# largemoteino1_1.net
KiCad netlist of a schematic drawn in EAGLE
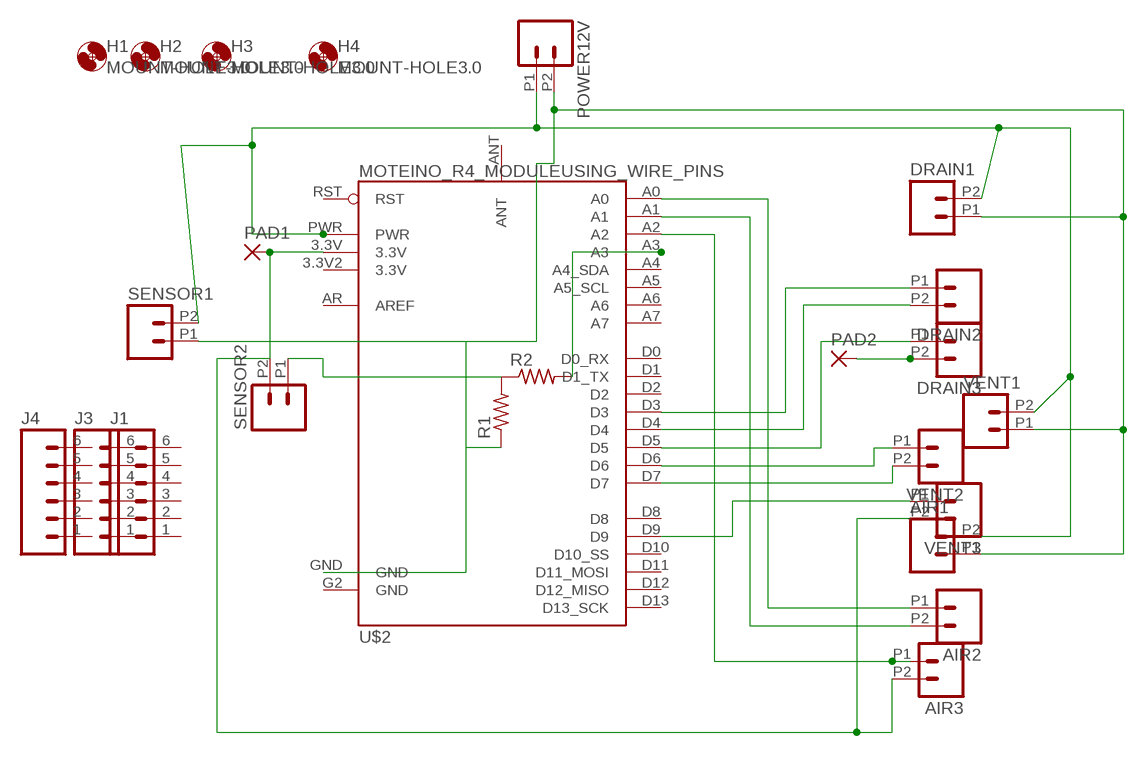
[diagram p0: schematic, sheet 1]

(export (version "E")
  (design (tool "Eeschema 10.0.6"))
  (components
    (comp (ref "AIR1")
      (value "M022.54MM_SCREWTERM")
      (footprint "eagle-import:1X02_2.54_SCREWTERM")
      (libsource (lib "eagle-import") (part "M022.54MM_SCREWTERM"))
    )
    (comp (ref "AIR2")
      (value "M022.54MM_SCREWTERM")
      (footprint "eagle-import:1X02_2.54_SCREWTERM")
      (libsource (lib "eagle-import") (part "M022.54MM_SCREWTERM"))
    )
    (comp (ref "AIR3")
      (value "M022.54MM_SCREWTERM")
      (footprint "eagle-import:1X02_2.54_SCREWTERM")
      (libsource (lib "eagle-import") (part "M022.54MM_SCREWTERM"))
    )
    (comp (ref "DRAIN1")
      (value "M022.54MM_SCREWTERM")
      (footprint "eagle-import:1X02_2.54_SCREWTERM")
      (libsource (lib "eagle-import") (part "M022.54MM_SCREWTERM"))
    )
    (comp (ref "DRAIN2")
      (value "M022.54MM_SCREWTERM")
      (footprint "eagle-import:1X02_2.54_SCREWTERM")
      (libsource (lib "eagle-import") (part "M022.54MM_SCREWTERM"))
    )
    (comp (ref "DRAIN3")
      (value "M022.54MM_SCREWTERM")
      (footprint "eagle-import:1X02_2.54_SCREWTERM")
      (libsource (lib "eagle-import") (part "M022.54MM_SCREWTERM"))
    )
    (comp (ref "H1")
      (value "MOUNT-HOLE3.0")
      (footprint "eagle-import:3,0")
      (libsource (lib "eagle-import") (part "MOUNT-HOLE3.0"))
    )
    (comp (ref "H2")
      (value "MOUNT-HOLE3.0")
      (footprint "eagle-import:3,0")
      (libsource (lib "eagle-import") (part "MOUNT-HOLE3.0"))
    )
    (comp (ref "H3")
      (value "MOUNT-HOLE3.0")
      (footprint "eagle-import:3,0")
      (libsource (lib "eagle-import") (part "MOUNT-HOLE3.0"))
    )
    (comp (ref "H4")
      (value "MOUNT-HOLE3.0")
      (footprint "eagle-import:3,0")
      (libsource (lib "eagle-import") (part "MOUNT-HOLE3.0"))
    )
    (comp (ref "J1")
      (value "M06LOCK_LONGPADS")
      (footprint "eagle-import:1X06_LOCK_LONGPADS")
      (libsource (lib "eagle-import") (part "M06LOCK_LONGPADS"))
    )
    (comp (ref "J3")
      (value "M06LOCK_LONGPADS")
      (footprint "eagle-import:1X06_LOCK_LONGPADS")
      (libsource (lib "eagle-import") (part "M06LOCK_LONGPADS"))
    )
    (comp (ref "J4")
      (value "M06LOCK_LONGPADS")
      (footprint "eagle-import:1X06_LOCK_LONGPADS")
      (libsource (lib "eagle-import") (part "M06LOCK_LONGPADS"))
    )
    (comp (ref "PAD1")
      (value "2,15/1,0")
      (footprint "eagle-import:2,15_1,0")
      (libsource (lib "eagle-import") (part "2,15/1,0"))
    )
    (comp (ref "PAD2")
      (value "2,15/1,0")
      (footprint "eagle-import:2,15_1,0")
      (libsource (lib "eagle-import") (part "2,15/1,0"))
    )
    (comp (ref "POWER12V")
      (value "M022.54MM_SCREWTERM")
      (footprint "eagle-import:1X02_2.54_SCREWTERM")
      (libsource (lib "eagle-import") (part "M022.54MM_SCREWTERM"))
    )
    (comp (ref "R1")
      (value "R-US_0207/10")
      (footprint "eagle-import:0207_10")
      (libsource (lib "eagle-import") (part "R-US_0207/10"))
    )
    (comp (ref "R2")
      (value "R-US_0207/10")
      (footprint "eagle-import:0207_10")
      (libsource (lib "eagle-import") (part "R-US_0207/10"))
    )
    (comp (ref "SENSOR1")
      (value "M022.54MM_SCREWTERM")
      (footprint "eagle-import:1X02_2.54_SCREWTERM")
      (libsource (lib "eagle-import") (part "M022.54MM_SCREWTERM"))
    )
    (comp (ref "SENSOR2")
      (value "M022.54MM_SCREWTERM")
      (footprint "eagle-import:1X02_2.54_SCREWTERM")
      (libsource (lib "eagle-import") (part "M022.54MM_SCREWTERM"))
    )
    (comp (ref "U$2")
      (value "MOTEINO_R4_MODULEUSING_WIRE_PINS")
      (footprint "eagle-import:MOTEINO_R4_WIRE")
      (libsource (lib "eagle-import") (part "MOTEINO_R4_MODULEUSING_WIRE_PINS"))
    )
    (comp (ref "VENT1")
      (value "M022.54MM_SCREWTERM")
      (footprint "eagle-import:1X02_2.54_SCREWTERM")
      (libsource (lib "eagle-import") (part "M022.54MM_SCREWTERM"))
    )
    (comp (ref "VENT2")
      (value "M022.54MM_SCREWTERM")
      (footprint "eagle-import:1X02_2.54_SCREWTERM")
      (libsource (lib "eagle-import") (part "M022.54MM_SCREWTERM"))
    )
    (comp (ref "VENT3")
      (value "M022.54MM_SCREWTERM")
      (footprint "eagle-import:1X02_2.54_SCREWTERM")
      (libsource (lib "eagle-import") (part "M022.54MM_SCREWTERM"))
    )
  )
  (nets
    (net (code "1") (name "/GND") (class "Default")
      (node (ref "U$2") (pin "G2") (pinfunction "GND_G2") (pintype "power_in"))
    )
    (net (code "2") (name "Net-(AIR1-1)") (class "Default")
      (node (ref "AIR1") (pin "P1") (pinfunction "1_P1") (pintype "passive"))
      (node (ref "DRAIN1") (pin "P1") (pinfunction "1_P1") (pintype "passive"))
      (node (ref "POWER12V") (pin "P2") (pinfunction "2_P2") (pintype "passive"))
      (node (ref "R1") (pin "1") (pinfunction "1_1") (pintype "passive"))
      (node (ref "SENSOR1") (pin "P1") (pinfunction "1_P1") (pintype "passive"))
      (node (ref "U$2") (pin "GND") (pinfunction "GND_GND") (pintype "power_in"))
      (node (ref "VENT1") (pin "P1") (pinfunction "1_P1") (pintype "passive"))
    )
    (net (code "3") (name "Net-(AIR1-2)") (class "Default")
      (node (ref "AIR1") (pin "P2") (pinfunction "2_P2") (pintype "passive"))
      (node (ref "DRAIN1") (pin "P2") (pinfunction "2_P2") (pintype "passive"))
      (node (ref "POWER12V") (pin "P1") (pinfunction "1_P1") (pintype "passive"))
      (node (ref "SENSOR1") (pin "P2") (pinfunction "2_P2") (pintype "passive"))
      (node (ref "U$2") (pin "PWR") (pinfunction "PWR_PWR") (pintype "passive"))
      (node (ref "VENT1") (pin "P2") (pinfunction "2_P2") (pintype "passive"))
    )
    (net (code "4") (name "Net-(AIR2-1)") (class "Default")
      (node (ref "AIR2") (pin "P1") (pinfunction "1_P1") (pintype "passive"))
      (node (ref "U$2") (pin "A0") (pinfunction "A0_A0") (pintype "bidirectional"))
    )
    (net (code "5") (name "Net-(AIR2-2)") (class "Default")
      (node (ref "AIR2") (pin "P2") (pinfunction "2_P2") (pintype "passive"))
      (node (ref "U$2") (pin "A1") (pinfunction "A1_A1") (pintype "bidirectional"))
    )
    (net (code "6") (name "Net-(AIR3-1)") (class "Default")
      (node (ref "AIR3") (pin "P1") (pinfunction "1_P1") (pintype "passive"))
      (node (ref "U$2") (pin "A2") (pinfunction "A2_A2") (pintype "bidirectional"))
    )
    (net (code "7") (name "Net-(AIR3-2)") (class "Default")
      (node (ref "AIR3") (pin "P2") (pinfunction "2_P2") (pintype "passive"))
      (node (ref "PAD1") (pin "1") (pinfunction "P_1") (pintype "passive"))
      (node (ref "SENSOR2") (pin "P2") (pinfunction "2_P2") (pintype "passive"))
      (node (ref "U$2") (pin "3.3V") (pinfunction "3.3V_3.3V") (pintype "passive"))
      (node (ref "VENT3") (pin "P2") (pinfunction "2_P2") (pintype "passive"))
    )
    (net (code "8") (name "Net-(DRAIN2-1)") (class "Default")
      (node (ref "DRAIN2") (pin "P1") (pinfunction "1_P1") (pintype "passive"))
      (node (ref "U$2") (pin "D3") (pinfunction "D3_D3") (pintype "bidirectional"))
    )
    (net (code "9") (name "Net-(DRAIN2-2)") (class "Default")
      (node (ref "DRAIN2") (pin "P2") (pinfunction "2_P2") (pintype "passive"))
      (node (ref "U$2") (pin "D4") (pinfunction "D4_D4") (pintype "bidirectional"))
    )
    (net (code "10") (name "Net-(DRAIN3-1)") (class "Default")
      (node (ref "DRAIN3") (pin "P1") (pinfunction "1_P1") (pintype "passive"))
      (node (ref "U$2") (pin "D5") (pinfunction "D5_D5") (pintype "bidirectional"))
    )
    (net (code "11") (name "Net-(DRAIN3-2)") (class "Default")
      (node (ref "DRAIN3") (pin "P2") (pinfunction "2_P2") (pintype "passive"))
      (node (ref "PAD2") (pin "1") (pinfunction "P_1") (pintype "passive"))
    )
    (net (code "12") (name "Net-(R2-Pad2)") (class "Default")
      (node (ref "R2") (pin "2") (pinfunction "2_2") (pintype "passive"))
      (node (ref "U$2") (pin "A3") (pinfunction "A3_A3") (pintype "bidirectional"))
    )
    (net (code "13") (name "Net-(SENSOR2-1)") (class "Default")
      (node (ref "R1") (pin "2") (pinfunction "2_2") (pintype "passive"))
      (node (ref "R2") (pin "1") (pinfunction "1_1") (pintype "passive"))
      (node (ref "SENSOR2") (pin "P1") (pinfunction "1_P1") (pintype "passive"))
    )
    (net (code "14") (name "Net-(VENT2-1)") (class "Default")
      (node (ref "U$2") (pin "D6") (pinfunction "D6_D6") (pintype "bidirectional"))
      (node (ref "VENT2") (pin "P1") (pinfunction "1_P1") (pintype "passive"))
    )
    (net (code "15") (name "Net-(VENT2-2)") (class "Default")
      (node (ref "U$2") (pin "D7") (pinfunction "D7_D7") (pintype "bidirectional"))
      (node (ref "VENT2") (pin "P2") (pinfunction "2_P2") (pintype "passive"))
    )
    (net (code "16") (name "Net-(VENT3-1)") (class "Default")
      (node (ref "U$2") (pin "D9") (pinfunction "D9_D9") (pintype "bidirectional"))
      (node (ref "VENT3") (pin "P1") (pinfunction "1_P1") (pintype "passive"))
    )
    (net (code "17") (name "unconnected-(J1-Pad1)") (class "Default")
      (node (ref "J1") (pin "1") (pinfunction "1_1") (pintype "passive"))
    )
    (net (code "18") (name "unconnected-(J1-Pad2)") (class "Default")
      (node (ref "J1") (pin "2") (pinfunction "2_2") (pintype "passive"))
    )
    (net (code "19") (name "unconnected-(J1-Pad3)") (class "Default")
      (node (ref "J1") (pin "3") (pinfunction "3_3") (pintype "passive"))
    )
    (net (code "20") (name "unconnected-(J1-Pad4)") (class "Default")
      (node (ref "J1") (pin "4") (pinfunction "4_4") (pintype "passive"))
    )
    (net (code "21") (name "unconnected-(J1-Pad5)") (class "Default")
      (node (ref "J1") (pin "5") (pinfunction "5_5") (pintype "passive"))
    )
    (net (code "22") (name "unconnected-(J1-Pad6)") (class "Default")
      (node (ref "J1") (pin "6") (pinfunction "6_6") (pintype "passive"))
    )
    (net (code "23") (name "unconnected-(J3-Pad1)") (class "Default")
      (node (ref "J3") (pin "1") (pinfunction "1_1") (pintype "passive"))
    )
    (net (code "24") (name "unconnected-(J3-Pad2)") (class "Default")
      (node (ref "J3") (pin "2") (pinfunction "2_2") (pintype "passive"))
    )
    (net (code "25") (name "unconnected-(J3-Pad3)") (class "Default")
      (node (ref "J3") (pin "3") (pinfunction "3_3") (pintype "passive"))
    )
    (net (code "26") (name "unconnected-(J3-Pad4)") (class "Default")
      (node (ref "J3") (pin "4") (pinfunction "4_4") (pintype "passive"))
    )
    (net (code "27") (name "unconnected-(J3-Pad5)") (class "Default")
      (node (ref "J3") (pin "5") (pinfunction "5_5") (pintype "passive"))
    )
    (net (code "28") (name "unconnected-(J3-Pad6)") (class "Default")
      (node (ref "J3") (pin "6") (pinfunction "6_6") (pintype "passive"))
    )
    (net (code "29") (name "unconnected-(J4-Pad1)") (class "Default")
      (node (ref "J4") (pin "1") (pinfunction "1_1") (pintype "passive"))
    )
    (net (code "30") (name "unconnected-(J4-Pad2)") (class "Default")
      (node (ref "J4") (pin "2") (pinfunction "2_2") (pintype "passive"))
    )
    (net (code "31") (name "unconnected-(J4-Pad3)") (class "Default")
      (node (ref "J4") (pin "3") (pinfunction "3_3") (pintype "passive"))
    )
    (net (code "32") (name "unconnected-(J4-Pad4)") (class "Default")
      (node (ref "J4") (pin "4") (pinfunction "4_4") (pintype "passive"))
    )
    (net (code "33") (name "unconnected-(J4-Pad5)") (class "Default")
      (node (ref "J4") (pin "5") (pinfunction "5_5") (pintype "passive"))
    )
    (net (code "34") (name "unconnected-(J4-Pad6)") (class "Default")
      (node (ref "J4") (pin "6") (pinfunction "6_6") (pintype "passive"))
    )
    (net (code "35") (name "unconnected-(U$2-3.3V-Pad3.3V2)") (class "Default")
      (node (ref "U$2") (pin "3.3V2") (pinfunction "3.3V_3.3V2") (pintype "passive"))
    )
    (net (code "36") (name "unconnected-(U$2-A4_SDA-PadA4)") (class "Default")
      (node (ref "U$2") (pin "A4") (pinfunction "A4_SDA_A4") (pintype "bidirectional"))
    )
    (net (code "37") (name "unconnected-(U$2-A5_SCL-PadA5)") (class "Default")
      (node (ref "U$2") (pin "A5") (pinfunction "A5_SCL_A5") (pintype "bidirectional"))
    )
    (net (code "38") (name "unconnected-(U$2-AREF-PadAR)") (class "Default")
      (node (ref "U$2") (pin "AR") (pinfunction "AREF_AR") (pintype "bidirectional"))
    )
    (net (code "39") (name "unconnected-(U$2-D0_RX-PadD0)") (class "Default")
      (node (ref "U$2") (pin "D0") (pinfunction "D0_RX_D0") (pintype "bidirectional"))
    )
    (net (code "40") (name "unconnected-(U$2-D1_TX-PadD1)") (class "Default")
      (node (ref "U$2") (pin "D1") (pinfunction "D1_TX_D1") (pintype "bidirectional"))
    )
    (net (code "41") (name "unconnected-(U$2-D10_SS-PadD10)") (class "Default")
      (node (ref "U$2") (pin "D10") (pinfunction "D10_SS_D10") (pintype "bidirectional"))
    )
    (net (code "42") (name "unconnected-(U$2-D11_MOSI-PadD11)") (class "Default")
      (node (ref "U$2") (pin "D11") (pinfunction "D11_MOSI_D11") (pintype "bidirectional"))
    )
    (net (code "43") (name "unconnected-(U$2-D12_MISO-PadD12)") (class "Default")
      (node (ref "U$2") (pin "D12") (pinfunction "D12_MISO_D12") (pintype "bidirectional"))
    )
    (net (code "44") (name "unconnected-(U$2-D13_SCK-PadD13)") (class "Default")
      (node (ref "U$2") (pin "D13") (pinfunction "D13_SCK_D13") (pintype "bidirectional"))
    )
    (net (code "45") (name "unconnected-(U$2-PadA6)") (class "Default")
      (node (ref "U$2") (pin "A6") (pinfunction "A6_A6") (pintype "bidirectional"))
    )
    (net (code "46") (name "unconnected-(U$2-PadA7)") (class "Default")
      (node (ref "U$2") (pin "A7") (pinfunction "A7_A7") (pintype "bidirectional"))
    )
    (net (code "47") (name "unconnected-(U$2-PadANT)") (class "Default")
      (node (ref "U$2") (pin "ANT") (pinfunction "ANT_ANT") (pintype "passive"))
    )
    (net (code "48") (name "unconnected-(U$2-PadD2)") (class "Default")
      (node (ref "U$2") (pin "D2") (pinfunction "D2_D2") (pintype "bidirectional"))
    )
    (net (code "49") (name "unconnected-(U$2-PadD8)") (class "Default")
      (node (ref "U$2") (pin "D8") (pinfunction "D8_D8") (pintype "bidirectional"))
    )
    (net (code "50") (name "unconnected-(U$2-PadRST)") (class "Default")
      (node (ref "U$2") (pin "RST") (pinfunction "RST_RST") (pintype "bidirectional"))
    )
  )
)
